# polarization_switch_mid_redo.net
KiCad netlist of a schematic drawn in EAGLE
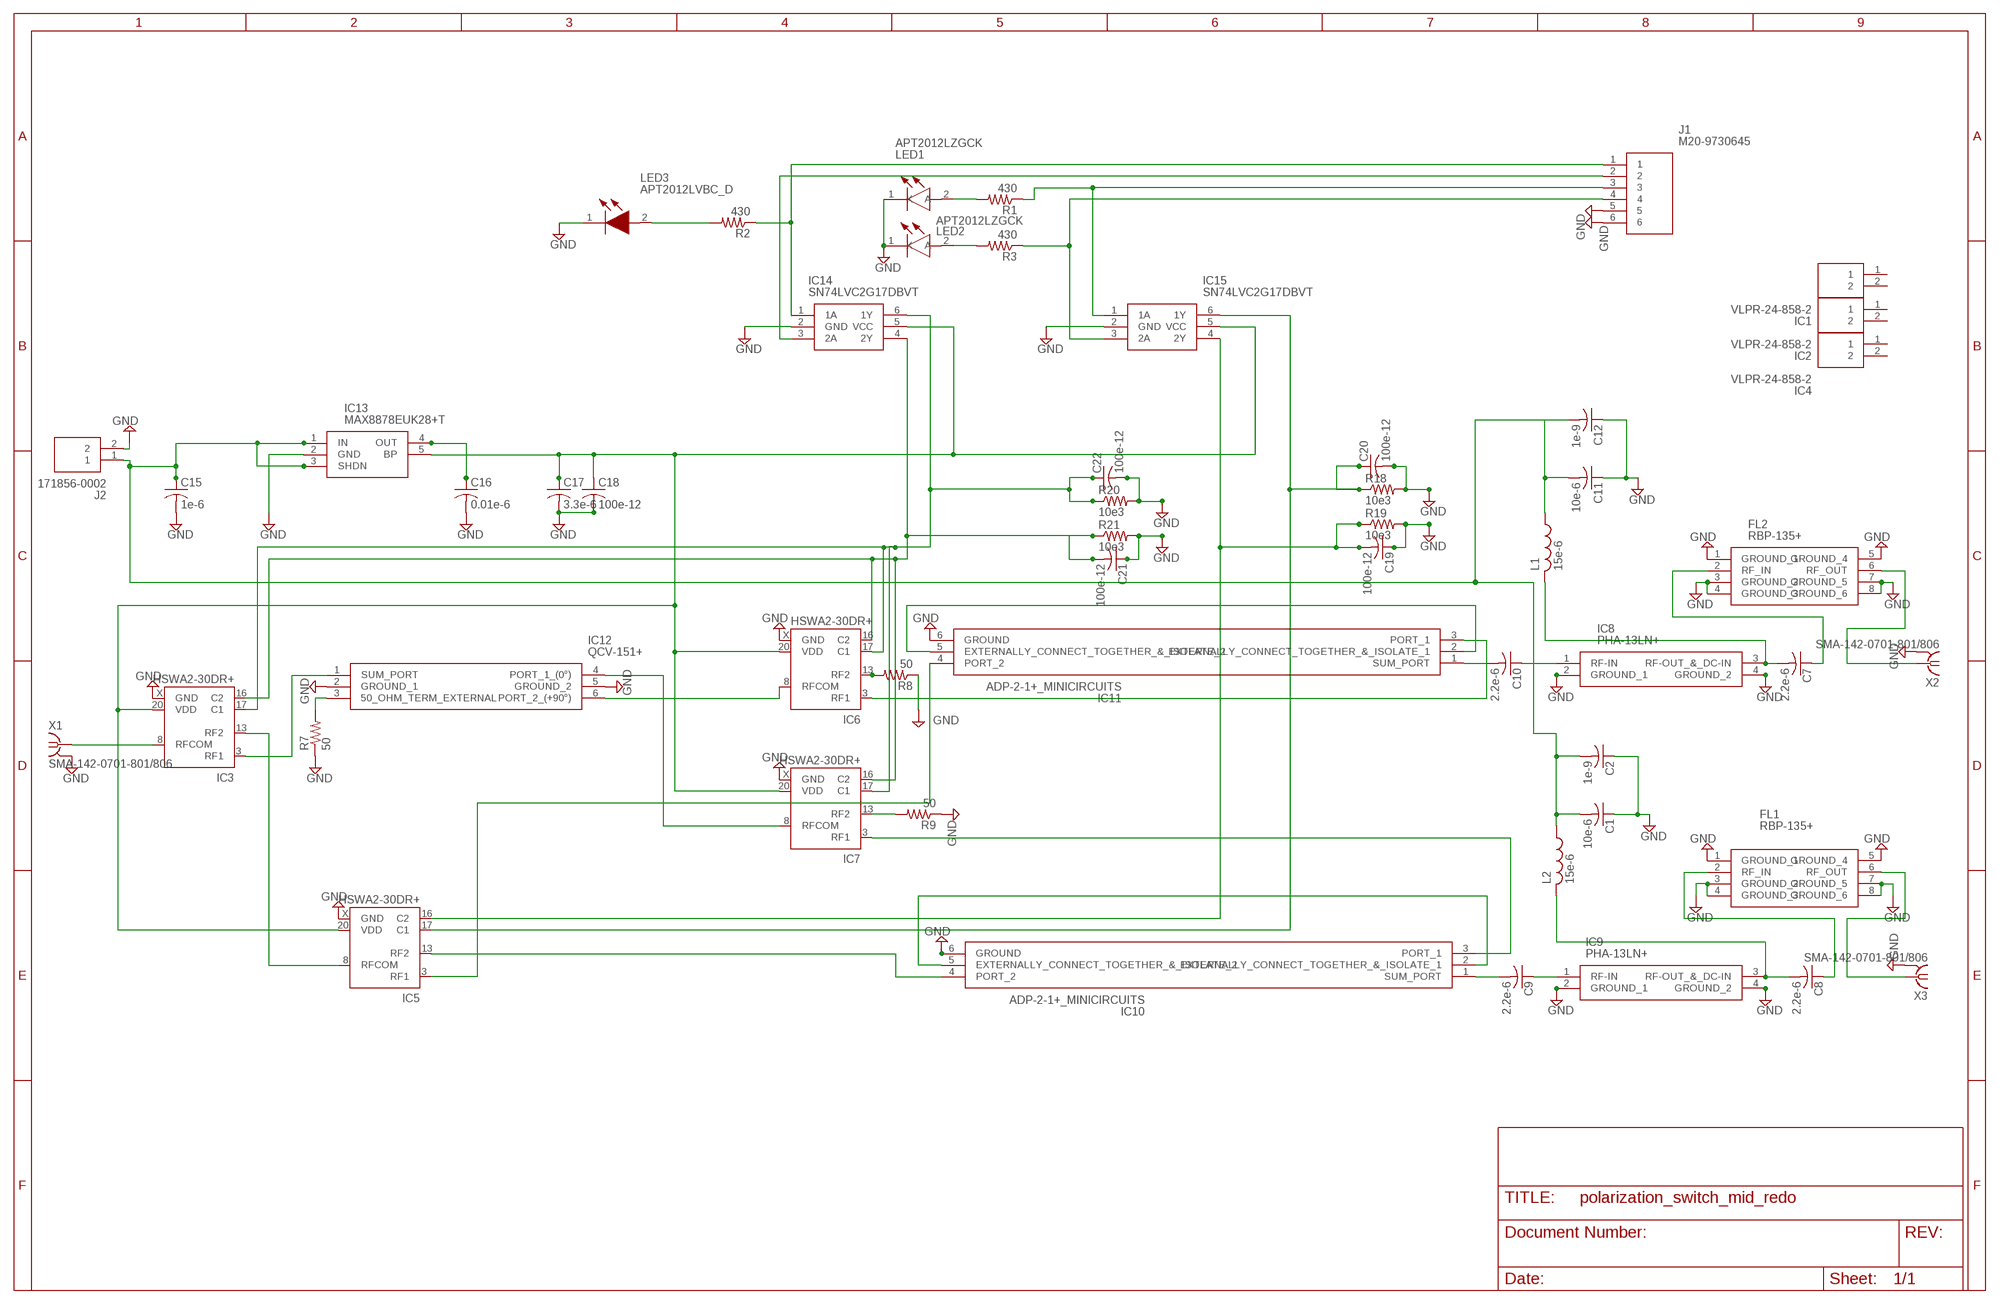
[diagram p0: schematic, sheet 1]

(export (version "E")
  (design (tool "Eeschema 10.0.6"))
  (components
    (comp (ref "C1")
      (value "10e-6")
      (footprint "eagle-import:C0603")
      (libsource (lib "eagle-import") (part "C-USC0603"))
    )
    (comp (ref "C2")
      (value "1e-9")
      (footprint "eagle-import:C0603")
      (libsource (lib "eagle-import") (part "C-USC0603"))
    )
    (comp (ref "C7")
      (value "2.2e-6")
      (footprint "eagle-import:C0603")
      (libsource (lib "eagle-import") (part "C-USC0603"))
    )
    (comp (ref "C8")
      (value "2.2e-6")
      (footprint "eagle-import:C0603")
      (libsource (lib "eagle-import") (part "C-USC0603"))
    )
    (comp (ref "C9")
      (value "2.2e-6")
      (footprint "eagle-import:C0603")
      (libsource (lib "eagle-import") (part "C-USC0603"))
    )
    (comp (ref "C10")
      (value "2.2e-6")
      (footprint "eagle-import:C0603")
      (libsource (lib "eagle-import") (part "C-USC0603"))
    )
    (comp (ref "C11")
      (value "10e-6")
      (footprint "eagle-import:C0603")
      (libsource (lib "eagle-import") (part "C-USC0603"))
    )
    (comp (ref "C12")
      (value "1e-9")
      (footprint "eagle-import:C0603")
      (libsource (lib "eagle-import") (part "C-USC0603"))
    )
    (comp (ref "C15")
      (value "1e-6")
      (footprint "eagle-import:C0603")
      (libsource (lib "eagle-import") (part "C-USC0603"))
    )
    (comp (ref "C16")
      (value "0.01e-6")
      (footprint "eagle-import:C0603")
      (libsource (lib "eagle-import") (part "C-USC0603"))
    )
    (comp (ref "C17")
      (value "3.3e-6")
      (footprint "eagle-import:C0603")
      (libsource (lib "eagle-import") (part "C-USC0603"))
    )
    (comp (ref "C18")
      (value "100e-12")
      (footprint "eagle-import:C0603")
      (libsource (lib "eagle-import") (part "C-USC0603"))
    )
    (comp (ref "C19")
      (value "100e-12")
      (footprint "eagle-import:C0603")
      (libsource (lib "eagle-import") (part "C-USC0603"))
    )
    (comp (ref "C20")
      (value "100e-12")
      (footprint "eagle-import:C0603")
      (libsource (lib "eagle-import") (part "C-USC0603"))
    )
    (comp (ref "C21")
      (value "100e-12")
      (footprint "eagle-import:C0603")
      (libsource (lib "eagle-import") (part "C-USC0603"))
    )
    (comp (ref "C22")
      (value "100e-12")
      (footprint "eagle-import:C0603")
      (libsource (lib "eagle-import") (part "C-USC0603"))
    )
    (comp (ref "FL1")
      (value "RBP-135+")
      (footprint "eagle-import:RBP135")
      (libsource (lib "eagle-import") (part "RBP-135+"))
    )
    (comp (ref "FL2")
      (value "RBP-135+")
      (footprint "eagle-import:RBP135")
      (libsource (lib "eagle-import") (part "RBP-135+"))
    )
    (comp (ref "IC1")
      (value "VLPR-24-858-2")
      (footprint "eagle-import:VLPR248582")
      (fields (field (name "RS_PART_NUMBER") "9063748"))
      (libsource (lib "eagle-import") (part "VLPR-24-858-2"))
    )
    (comp (ref "IC2")
      (value "VLPR-24-858-2")
      (footprint "eagle-import:VLPR248582")
      (fields (field (name "RS_PART_NUMBER") "9063748"))
      (libsource (lib "eagle-import") (part "VLPR-24-858-2"))
    )
    (comp (ref "IC3")
      (value "HSWA2-30DR+")
      (footprint "eagle-import:DG983-1")
      (libsource (lib "eagle-import") (part "HSWA2-30DR+"))
    )
    (comp (ref "IC4")
      (value "VLPR-24-858-2")
      (footprint "eagle-import:VLPR248582")
      (fields (field (name "RS_PART_NUMBER") "9063748"))
      (libsource (lib "eagle-import") (part "VLPR-24-858-2"))
    )
    (comp (ref "IC5")
      (value "HSWA2-30DR+")
      (footprint "eagle-import:DG983-1")
      (libsource (lib "eagle-import") (part "HSWA2-30DR+"))
    )
    (comp (ref "IC6")
      (value "HSWA2-30DR+")
      (footprint "eagle-import:DG983-1")
      (libsource (lib "eagle-import") (part "HSWA2-30DR+"))
    )
    (comp (ref "IC7")
      (value "HSWA2-30DR+")
      (footprint "eagle-import:DG983-1")
      (libsource (lib "eagle-import") (part "HSWA2-30DR+"))
    )
    (comp (ref "IC8")
      (value "PHA-13LN+")
      (footprint "eagle-import:PHA13LN")
      (libsource (lib "eagle-import") (part "PHA-13LN+"))
    )
    (comp (ref "IC9")
      (value "PHA-13LN+")
      (footprint "eagle-import:PHA13LN")
      (libsource (lib "eagle-import") (part "PHA-13LN+"))
    )
    (comp (ref "IC10")
      (value "ADP-2-1+_MINICIRCUITS")
      (footprint "eagle-import:SOTFL254P691X411-6N")
      (fields (field (name "MANUFACTURER_PART_NUMBER") "ADP-2-1+ MINICIRCUITS"))
      (libsource (lib "eagle-import") (part "ADP-2-1+_MINICIRCUITS"))
    )
    (comp (ref "IC11")
      (value "ADP-2-1+_MINICIRCUITS")
      (footprint "eagle-import:SOTFL254P691X411-6N")
      (fields (field (name "MANUFACTURER_PART_NUMBER") "ADP-2-1+ MINICIRCUITS"))
      (libsource (lib "eagle-import") (part "ADP-2-1+_MINICIRCUITS"))
    )
    (comp (ref "IC12")
      (value "QCV-151+")
      (footprint "eagle-import:QCV151")
      (libsource (lib "eagle-import") (part "QCV-151+"))
    )
    (comp (ref "IC13")
      (value "MAX8878EUK28+T")
      (footprint "eagle-import:SOT95P280X145-5N")
      (libsource (lib "eagle-import") (part "MAX8878EUK28+T"))
    )
    (comp (ref "IC14")
      (value "SN74LVC2G17DBVT")
      (footprint "eagle-import:SOT95P280X145-6N")
      (fields
        (field (name "MOUSER_PART_NUMBER") "595-SN74LVC2G17DBVT")
        (field (name "RS_PART_NUMBER") "6628944P")
      )
      (libsource (lib "eagle-import") (part "SN74LVC2G17DBVT"))
    )
    (comp (ref "IC15")
      (value "SN74LVC2G17DBVT")
      (footprint "eagle-import:SOT95P280X145-6N")
      (fields
        (field (name "MOUSER_PART_NUMBER") "595-SN74LVC2G17DBVT")
        (field (name "RS_PART_NUMBER") "6628944P")
      )
      (libsource (lib "eagle-import") (part "SN74LVC2G17DBVT"))
    )
    (comp (ref "J1")
      (value "M20-9730645")
      (footprint "eagle-import:HDRV6W66P0X254_1X6_1524X254X96")
      (fields (field (name "MOUSER_PART_NUMBER") "855-M20-9730645"))
      (libsource (lib "eagle-import") (part "M20-9730645"))
    )
    (comp (ref "J2")
      (value "171856-0002")
      (footprint "eagle-import:SHDR2W90P0X254_1X2_493X635X106")
      (fields
        (field (name "MOUSER_PART_NUMBER") "538-171856-0002")
        (field (name "RS_PART_NUMBER") "7922884P")
      )
      (libsource (lib "eagle-import") (part "171856-0002"))
    )
    (comp (ref "L1")
      (value "15e-6")
      (footprint "eagle-import:L3225M")
      (libsource (lib "eagle-import") (part "L-USL3225M"))
    )
    (comp (ref "L2")
      (value "15e-6")
      (footprint "eagle-import:L3225M")
      (libsource (lib "eagle-import") (part "L-USL3225M"))
    )
    (comp (ref "LED1")
      (value "APT2012LZGCK")
      (footprint "eagle-import:LEDC2012X85N")
      (fields (field (name "MOUSER_PART_NUMBER") "604-APT2012LZGCK"))
      (libsource (lib "eagle-import") (part "APT2012LZGCK"))
    )
    (comp (ref "LED2")
      (value "APT2012LZGCK")
      (footprint "eagle-import:LEDC2012X85N")
      (fields (field (name "MOUSER_PART_NUMBER") "604-APT2012LZGCK"))
      (libsource (lib "eagle-import") (part "APT2012LZGCK"))
    )
    (comp (ref "LED3")
      (value "APT2012LVBC_D")
      (footprint "eagle-import:LEDC2012X85N")
      (fields
        (field (name "ARROW_PART_NUMBER") "APT2012LVBC/D")
        (field (name "MOUSER_PART_NUMBER") "604-APT2012LVBCD")
      )
      (libsource (lib "eagle-import") (part "APT2012LVBC_D"))
    )
    (comp (ref "R1")
      (value "430")
      (footprint "eagle-import:R0603")
      (libsource (lib "eagle-import") (part "R-US_R0603"))
    )
    (comp (ref "R2")
      (value "430")
      (footprint "eagle-import:R0603")
      (libsource (lib "eagle-import") (part "R-US_R0603"))
    )
    (comp (ref "R3")
      (value "430")
      (footprint "eagle-import:R0603")
      (libsource (lib "eagle-import") (part "R-US_R0603"))
    )
    (comp (ref "R7")
      (value "50")
      (footprint "eagle-import:R0603")
      (libsource (lib "eagle-import") (part "R-US_R0603"))
    )
    (comp (ref "R8")
      (value "50")
      (footprint "eagle-import:R0603")
      (libsource (lib "eagle-import") (part "R-US_R0603"))
    )
    (comp (ref "R9")
      (value "50")
      (footprint "eagle-import:R0603")
      (libsource (lib "eagle-import") (part "R-US_R0603"))
    )
    (comp (ref "R18")
      (value "10e3")
      (footprint "eagle-import:R0603")
      (libsource (lib "eagle-import") (part "R-US_R0603"))
    )
    (comp (ref "R19")
      (value "10e3")
      (footprint "eagle-import:R0603")
      (libsource (lib "eagle-import") (part "R-US_R0603"))
    )
    (comp (ref "R20")
      (value "10e3")
      (footprint "eagle-import:R0603")
      (libsource (lib "eagle-import") (part "R-US_R0603"))
    )
    (comp (ref "R21")
      (value "10e3")
      (footprint "eagle-import:R0603")
      (libsource (lib "eagle-import") (part "R-US_R0603"))
    )
    (comp (ref "X1")
      (value "SMA-142-0701-801/806")
      (footprint "eagle-import:J502-ND-142-0701-801_806")
      (fields (field (name "MF") "JOHNSON COMPONENTS") (field (name "MPN") "142-0701-801"))
      (libsource (lib "eagle-import") (part "SMA-142-0701-801/806"))
    )
    (comp (ref "X2")
      (value "SMA-142-0701-801/806")
      (footprint "eagle-import:J502-ND-142-0701-801_806")
      (fields (field (name "MF") "JOHNSON COMPONENTS") (field (name "MPN") "142-0701-801"))
      (libsource (lib "eagle-import") (part "SMA-142-0701-801/806"))
    )
    (comp (ref "X3")
      (value "SMA-142-0701-801/806")
      (footprint "eagle-import:J502-ND-142-0701-801_806")
      (fields (field (name "MF") "JOHNSON COMPONENTS") (field (name "MPN") "142-0701-801"))
      (libsource (lib "eagle-import") (part "SMA-142-0701-801/806"))
    )
  )
  (nets
    (net (code "1") (name "GND") (class "Default")
      (node (ref "C1") (pin "1") (pinfunction "1_1") (pintype "passive"))
      (node (ref "C11") (pin "1") (pinfunction "1_1") (pintype "passive"))
      (node (ref "C12") (pin "1") (pinfunction "1_1") (pintype "passive"))
      (node (ref "C15") (pin "2") (pinfunction "2_2") (pintype "passive"))
      (node (ref "C16") (pin "2") (pinfunction "2_2") (pintype "passive"))
      (node (ref "C17") (pin "2") (pinfunction "2_2") (pintype "passive"))
      (node (ref "C18") (pin "2") (pinfunction "2_2") (pintype "passive"))
      (node (ref "C19") (pin "1") (pinfunction "1_1") (pintype "passive"))
      (node (ref "C2") (pin "1") (pinfunction "1_1") (pintype "passive"))
      (node (ref "C20") (pin "2") (pinfunction "2_2") (pintype "passive"))
      (node (ref "C21") (pin "1") (pinfunction "1_1") (pintype "passive"))
      (node (ref "C22") (pin "2") (pinfunction "2_2") (pintype "passive"))
      (node (ref "FL1") (pin "1") (pinfunction "GROUND_1_1") (pintype "bidirectional"))
      (node (ref "FL1") (pin "3") (pinfunction "GROUND_2_3") (pintype "bidirectional"))
      (node (ref "FL1") (pin "4") (pinfunction "GROUND_3_4") (pintype "bidirectional"))
      (node (ref "FL1") (pin "5") (pinfunction "GROUND_4_5") (pintype "bidirectional"))
      (node (ref "FL1") (pin "7") (pinfunction "GROUND_5_7") (pintype "bidirectional"))
      (node (ref "FL1") (pin "8") (pinfunction "GROUND_6_8") (pintype "bidirectional"))
      (node (ref "FL2") (pin "1") (pinfunction "GROUND_1_1") (pintype "bidirectional"))
      (node (ref "FL2") (pin "3") (pinfunction "GROUND_2_3") (pintype "bidirectional"))
      (node (ref "FL2") (pin "4") (pinfunction "GROUND_3_4") (pintype "bidirectional"))
      (node (ref "FL2") (pin "5") (pinfunction "GROUND_4_5") (pintype "bidirectional"))
      (node (ref "FL2") (pin "7") (pinfunction "GROUND_5_7") (pintype "bidirectional"))
      (node (ref "FL2") (pin "8") (pinfunction "GROUND_6_8") (pintype "bidirectional"))
      (node (ref "IC10") (pin "6") (pinfunction "GROUND_6") (pintype "bidirectional"))
      (node (ref "IC11") (pin "6") (pinfunction "GROUND_6") (pintype "bidirectional"))
      (node (ref "IC12") (pin "2") (pinfunction "GROUND_1_2") (pintype "bidirectional"))
      (node (ref "IC12") (pin "5") (pinfunction "GROUND_2_5") (pintype "bidirectional"))
      (node (ref "IC13") (pin "2") (pinfunction "GND_2") (pintype "power_in"))
      (node (ref "IC14") (pin "2") (pinfunction "GND_2") (pintype "bidirectional"))
      (node (ref "IC15") (pin "2") (pinfunction "GND_2") (pintype "bidirectional"))
      (node (ref "IC3") (pin "X") (pinfunction "GND_X") (pintype "power_in"))
      (node (ref "IC5") (pin "X") (pinfunction "GND_X") (pintype "power_in"))
      (node (ref "IC6") (pin "X") (pinfunction "GND_X") (pintype "power_in"))
      (node (ref "IC7") (pin "X") (pinfunction "GND_X") (pintype "power_in"))
      (node (ref "IC8") (pin "2") (pinfunction "GROUND_1_2") (pintype "bidirectional"))
      (node (ref "IC8") (pin "4") (pinfunction "GROUND_2_4") (pintype "bidirectional"))
      (node (ref "IC9") (pin "2") (pinfunction "GROUND_1_2") (pintype "bidirectional"))
      (node (ref "IC9") (pin "4") (pinfunction "GROUND_2_4") (pintype "bidirectional"))
      (node (ref "J1") (pin "5") (pinfunction "5_5") (pintype "bidirectional"))
      (node (ref "J1") (pin "6") (pinfunction "6_6") (pintype "bidirectional"))
      (node (ref "J2") (pin "2") (pinfunction "2_2") (pintype "bidirectional"))
      (node (ref "LED1") (pin "1") (pinfunction "K_1") (pintype "bidirectional"))
      (node (ref "LED2") (pin "1") (pinfunction "K_1") (pintype "bidirectional"))
      (node (ref "LED3") (pin "1") (pinfunction "K_1") (pintype "bidirectional"))
      (node (ref "R18") (pin "2") (pinfunction "2_2") (pintype "passive"))
      (node (ref "R19") (pin "2") (pinfunction "2_2") (pintype "passive"))
      (node (ref "R20") (pin "2") (pinfunction "2_2") (pintype "passive"))
      (node (ref "R21") (pin "2") (pinfunction "2_2") (pintype "passive"))
      (node (ref "R7") (pin "1") (pinfunction "1_1") (pintype "passive"))
      (node (ref "R8") (pin "1") (pinfunction "1_1") (pintype "passive"))
      (node (ref "R9") (pin "1") (pinfunction "1_1") (pintype "passive"))
      (node (ref "X1") (pin "G@1") (pinfunction "2_G@1") (pintype "passive"))
      (node (ref "X1") (pin "G@2") (pinfunction "2_G@2") (pintype "passive"))
      (node (ref "X1") (pin "G@3") (pinfunction "2_G@3") (pintype "passive"))
      (node (ref "X1") (pin "G@4") (pinfunction "2_G@4") (pintype "passive"))
      (node (ref "X2") (pin "G@1") (pinfunction "2_G@1") (pintype "passive"))
      (node (ref "X2") (pin "G@2") (pinfunction "2_G@2") (pintype "passive"))
      (node (ref "X2") (pin "G@3") (pinfunction "2_G@3") (pintype "passive"))
      (node (ref "X2") (pin "G@4") (pinfunction "2_G@4") (pintype "passive"))
      (node (ref "X3") (pin "G@1") (pinfunction "2_G@1") (pintype "passive"))
      (node (ref "X3") (pin "G@2") (pinfunction "2_G@2") (pintype "passive"))
      (node (ref "X3") (pin "G@3") (pinfunction "2_G@3") (pintype "passive"))
      (node (ref "X3") (pin "G@4") (pinfunction "2_G@4") (pintype "passive"))
    )
    (net (code "2") (name "Net-(FL1-RF_IN)") (class "Default")
      (node (ref "C8") (pin "1") (pinfunction "1_1") (pintype "passive"))
      (node (ref "FL1") (pin "2") (pinfunction "RF_IN_2") (pintype "bidirectional"))
    )
    (net (code "3") (name "Net-(FL1-RF_OUT)") (class "Default")
      (node (ref "FL1") (pin "6") (pinfunction "RF_OUT_6") (pintype "bidirectional"))
      (node (ref "X3") (pin "1") (pinfunction "1_1") (pintype "passive"))
    )
    (net (code "4") (name "Net-(FL2-RF_IN)") (class "Default")
      (node (ref "C7") (pin "1") (pinfunction "1_1") (pintype "passive"))
      (node (ref "FL2") (pin "2") (pinfunction "RF_IN_2") (pintype "bidirectional"))
    )
    (net (code "5") (name "Net-(FL2-RF_OUT)") (class "Default")
      (node (ref "FL2") (pin "6") (pinfunction "RF_OUT_6") (pintype "bidirectional"))
      (node (ref "X2") (pin "1") (pinfunction "1_1") (pintype "passive"))
    )
    (net (code "6") (name "Net-(IC3A-RF2)") (class "Default")
      (node (ref "IC3") (pin "13") (pinfunction "RF2_13") (pintype "passive"))
      (node (ref "IC5") (pin "8") (pinfunction "RFCOM_8") (pintype "passive"))
    )
    (net (code "7") (name "Net-(IC3A-RFCOM)") (class "Default")
      (node (ref "IC3") (pin "8") (pinfunction "RFCOM_8") (pintype "passive"))
      (node (ref "X1") (pin "1") (pinfunction "1_1") (pintype "passive"))
    )
    (net (code "8") (name "Net-(IC6A-RF2)") (class "Default")
      (node (ref "IC6") (pin "13") (pinfunction "RF2_13") (pintype "passive"))
      (node (ref "R8") (pin "2") (pinfunction "2_2") (pintype "passive"))
    )
    (net (code "9") (name "Net-(IC7A-RF2)") (class "Default")
      (node (ref "IC7") (pin "13") (pinfunction "RF2_13") (pintype "passive"))
      (node (ref "R9") (pin "2") (pinfunction "2_2") (pintype "passive"))
    )
    (net (code "10") (name "Net-(IC8-RF-IN)") (class "Default")
      (node (ref "C10") (pin "1") (pinfunction "1_1") (pintype "passive"))
      (node (ref "IC8") (pin "1") (pinfunction "RF-IN_1") (pintype "bidirectional"))
    )
    (net (code "11") (name "Net-(IC8-RF-OUT_&_DC-IN)") (class "Default")
      (node (ref "C7") (pin "2") (pinfunction "2_2") (pintype "passive"))
      (node (ref "IC8") (pin "3") (pinfunction "RF-OUT_&_DC-IN_3") (pintype "bidirectional"))
      (node (ref "L1") (pin "2") (pinfunction "2_2") (pintype "passive"))
    )
    (net (code "12") (name "Net-(IC9-RF-IN)") (class "Default")
      (node (ref "C9") (pin "1") (pinfunction "1_1") (pintype "passive"))
      (node (ref "IC9") (pin "1") (pinfunction "RF-IN_1") (pintype "bidirectional"))
    )
    (net (code "13") (name "Net-(IC9-RF-OUT_&_DC-IN)") (class "Default")
      (node (ref "C8") (pin "2") (pinfunction "2_2") (pintype "passive"))
      (node (ref "IC9") (pin "3") (pinfunction "RF-OUT_&_DC-IN_3") (pintype "bidirectional"))
      (node (ref "L2") (pin "2") (pinfunction "2_2") (pintype "passive"))
    )
    (net (code "14") (name "Net-(IC10-EXTERNALLY_CONNECT_TOGETHER_&_ISOLATE_1)") (class "Default")
      (node (ref "IC10") (pin "2") (pinfunction "EXTERNALLY_CONNECT_TOGETHER_&_ISOLATE_1_2") (pintype "bidirectional"))
      (node (ref "IC10") (pin "5") (pinfunction "EXTERNALLY_CONNECT_TOGETHER_&_ISOLATE_2_5") (pintype "bidirectional"))
    )
    (net (code "15") (name "Net-(IC10-PORT_1)") (class "Default")
      (node (ref "IC10") (pin "3") (pinfunction "PORT_1_3") (pintype "bidirectional"))
      (node (ref "IC7") (pin "3") (pinfunction "RF1_3") (pintype "passive"))
    )
    (net (code "16") (name "Net-(IC10-PORT_2)") (class "Default")
      (node (ref "IC10") (pin "4") (pinfunction "PORT_2_4") (pintype "bidirectional"))
      (node (ref "IC5") (pin "13") (pinfunction "RF2_13") (pintype "passive"))
    )
    (net (code "17") (name "Net-(IC10-SUM_PORT)") (class "Default")
      (node (ref "C9") (pin "2") (pinfunction "2_2") (pintype "passive"))
      (node (ref "IC10") (pin "1") (pinfunction "SUM_PORT_1") (pintype "bidirectional"))
    )
    (net (code "18") (name "Net-(IC11-EXTERNALLY_CONNECT_TOGETHER_&_ISOLATE_1)") (class "Default")
      (node (ref "IC11") (pin "2") (pinfunction "EXTERNALLY_CONNECT_TOGETHER_&_ISOLATE_1_2") (pintype "bidirectional"))
      (node (ref "IC11") (pin "5") (pinfunction "EXTERNALLY_CONNECT_TOGETHER_&_ISOLATE_2_5") (pintype "bidirectional"))
    )
    (net (code "19") (name "Net-(IC11-PORT_1)") (class "Default")
      (node (ref "IC11") (pin "3") (pinfunction "PORT_1_3") (pintype "bidirectional"))
      (node (ref "IC6") (pin "3") (pinfunction "RF1_3") (pintype "passive"))
    )
    (net (code "20") (name "Net-(IC11-PORT_2)") (class "Default")
      (node (ref "IC11") (pin "4") (pinfunction "PORT_2_4") (pintype "bidirectional"))
      (node (ref "IC5") (pin "3") (pinfunction "RF1_3") (pintype "passive"))
    )
    (net (code "21") (name "Net-(IC11-SUM_PORT)") (class "Default")
      (node (ref "C10") (pin "2") (pinfunction "2_2") (pintype "passive"))
      (node (ref "IC11") (pin "1") (pinfunction "SUM_PORT_1") (pintype "bidirectional"))
    )
    (net (code "22") (name "Net-(IC12-50_OHM_TERM_EXTERNAL)") (class "Default")
      (node (ref "IC12") (pin "3") (pinfunction "50_OHM_TERM_EXTERNAL_3") (pintype "bidirectional"))
      (node (ref "R7") (pin "2") (pinfunction "2_2") (pintype "passive"))
    )
    (net (code "23") (name "Net-(IC12-PORT_1_(0°))") (class "Default")
      (node (ref "IC12") (pin "4") (pinfunction "PORT_1_(0°)_4") (pintype "bidirectional"))
      (node (ref "IC7") (pin "8") (pinfunction "RFCOM_8") (pintype "passive"))
    )
    (net (code "24") (name "Net-(IC12-PORT_2_(+90°))") (class "Default")
      (node (ref "IC12") (pin "6") (pinfunction "PORT_2_(+90°)_6") (pintype "bidirectional"))
      (node (ref "IC6") (pin "8") (pinfunction "RFCOM_8") (pintype "passive"))
    )
    (net (code "25") (name "Net-(IC12-SUM_PORT)") (class "Default")
      (node (ref "IC12") (pin "1") (pinfunction "SUM_PORT_1") (pintype "bidirectional"))
      (node (ref "IC3") (pin "3") (pinfunction "RF1_3") (pintype "passive"))
    )
    (net (code "26") (name "Net-(IC13-BP)") (class "Default")
      (node (ref "C17") (pin "1") (pinfunction "1_1") (pintype "passive"))
      (node (ref "C18") (pin "1") (pinfunction "1_1") (pintype "passive"))
      (node (ref "IC13") (pin "5") (pinfunction "BP_5") (pintype "bidirectional"))
      (node (ref "IC14") (pin "5") (pinfunction "VCC_5") (pintype "bidirectional"))
      (node (ref "IC15") (pin "5") (pinfunction "VCC_5") (pintype "bidirectional"))
      (node (ref "IC3") (pin "20") (pinfunction "VDD_20") (pintype "input"))
      (node (ref "IC5") (pin "20") (pinfunction "VDD_20") (pintype "input"))
      (node (ref "IC6") (pin "20") (pinfunction "VDD_20") (pintype "input"))
      (node (ref "IC7") (pin "20") (pinfunction "VDD_20") (pintype "input"))
    )
    (net (code "27") (name "Net-(IC13-IN)") (class "Default")
      (node (ref "C1") (pin "2") (pinfunction "2_2") (pintype "passive"))
      (node (ref "C11") (pin "2") (pinfunction "2_2") (pintype "passive"))
      (node (ref "C12") (pin "2") (pinfunction "2_2") (pintype "passive"))
      (node (ref "C15") (pin "1") (pinfunction "1_1") (pintype "passive"))
      (node (ref "C2") (pin "2") (pinfunction "2_2") (pintype "passive"))
      (node (ref "IC13") (pin "1") (pinfunction "IN_1") (pintype "input"))
      (node (ref "IC13") (pin "3") (pinfunction "SHDN_3") (pintype "bidirectional"))
      (node (ref "J2") (pin "1") (pinfunction "1_1") (pintype "bidirectional"))
      (node (ref "L1") (pin "1") (pinfunction "1_1") (pintype "passive"))
      (node (ref "L2") (pin "1") (pinfunction "1_1") (pintype "passive"))
    )
    (net (code "28") (name "Net-(IC13-OUT)") (class "Default")
      (node (ref "C16") (pin "1") (pinfunction "1_1") (pintype "passive"))
      (node (ref "IC13") (pin "4") (pinfunction "OUT_4") (pintype "output"))
    )
    (net (code "29") (name "Net-(IC14-1A)") (class "Default")
      (node (ref "IC14") (pin "1") (pinfunction "1A_1") (pintype "bidirectional"))
      (node (ref "J1") (pin "1") (pinfunction "1_1") (pintype "bidirectional"))
      (node (ref "R2") (pin "1") (pinfunction "1_1") (pintype "passive"))
    )
    (net (code "30") (name "Net-(IC14-1Y)") (class "Default")
      (node (ref "C22") (pin "1") (pinfunction "1_1") (pintype "passive"))
      (node (ref "IC14") (pin "6") (pinfunction "1Y_6") (pintype "bidirectional"))
      (node (ref "IC3") (pin "17") (pinfunction "C1_17") (pintype "passive"))
      (node (ref "IC6") (pin "17") (pinfunction "C1_17") (pintype "passive"))
      (node (ref "IC7") (pin "17") (pinfunction "C1_17") (pintype "passive"))
      (node (ref "R20") (pin "1") (pinfunction "1_1") (pintype "passive"))
    )
    (net (code "31") (name "Net-(IC14-2A)") (class "Default")
      (node (ref "IC14") (pin "3") (pinfunction "2A_3") (pintype "bidirectional"))
      (node (ref "J1") (pin "2") (pinfunction "2_2") (pintype "bidirectional"))
    )
    (net (code "32") (name "Net-(IC14-2Y)") (class "Default")
      (node (ref "C21") (pin "2") (pinfunction "2_2") (pintype "passive"))
      (node (ref "IC14") (pin "4") (pinfunction "2Y_4") (pintype "bidirectional"))
      (node (ref "IC3") (pin "16") (pinfunction "C2_16") (pintype "passive"))
      (node (ref "IC6") (pin "16") (pinfunction "C2_16") (pintype "passive"))
      (node (ref "IC7") (pin "16") (pinfunction "C2_16") (pintype "passive"))
      (node (ref "R21") (pin "1") (pinfunction "1_1") (pintype "passive"))
    )
    (net (code "33") (name "Net-(IC15-1A)") (class "Default")
      (node (ref "IC15") (pin "1") (pinfunction "1A_1") (pintype "bidirectional"))
      (node (ref "J1") (pin "3") (pinfunction "3_3") (pintype "bidirectional"))
      (node (ref "R1") (pin "1") (pinfunction "1_1") (pintype "passive"))
    )
    (net (code "34") (name "Net-(IC15-1Y)") (class "Default")
      (node (ref "C20") (pin "1") (pinfunction "1_1") (pintype "passive"))
      (node (ref "IC15") (pin "6") (pinfunction "1Y_6") (pintype "bidirectional"))
      (node (ref "IC5") (pin "17") (pinfunction "C1_17") (pintype "passive"))
      (node (ref "R18") (pin "1") (pinfunction "1_1") (pintype "passive"))
    )
    (net (code "35") (name "Net-(IC15-2A)") (class "Default")
      (node (ref "IC15") (pin "3") (pinfunction "2A_3") (pintype "bidirectional"))
      (node (ref "J1") (pin "4") (pinfunction "4_4") (pintype "bidirectional"))
      (node (ref "R3") (pin "1") (pinfunction "1_1") (pintype "passive"))
    )
    (net (code "36") (name "Net-(IC15-2Y)") (class "Default")
      (node (ref "C19") (pin "2") (pinfunction "2_2") (pintype "passive"))
      (node (ref "IC15") (pin "4") (pinfunction "2Y_4") (pintype "bidirectional"))
      (node (ref "IC5") (pin "16") (pinfunction "C2_16") (pintype "passive"))
      (node (ref "R19") (pin "1") (pinfunction "1_1") (pintype "passive"))
    )
    (net (code "37") (name "Net-(LED1-A)") (class "Default")
      (node (ref "LED1") (pin "2") (pinfunction "A_2") (pintype "bidirectional"))
      (node (ref "R1") (pin "2") (pinfunction "2_2") (pintype "passive"))
    )
    (net (code "38") (name "Net-(LED2-A)") (class "Default")
      (node (ref "LED2") (pin "2") (pinfunction "A_2") (pintype "bidirectional"))
      (node (ref "R3") (pin "2") (pinfunction "2_2") (pintype "passive"))
    )
    (net (code "39") (name "Net-(LED3-A)") (class "Default")
      (node (ref "LED3") (pin "2") (pinfunction "A_2") (pintype "bidirectional"))
      (node (ref "R2") (pin "2") (pinfunction "2_2") (pintype "passive"))
    )
    (net (code "40") (name "unconnected-(IC1-Pad1)") (class "Default")
      (node (ref "IC1") (pin "1") (pinfunction "1_1") (pintype "bidirectional"))
    )
    (net (code "41") (name "unconnected-(IC1-Pad2)") (class "Default")
      (node (ref "IC1") (pin "2") (pinfunction "2_2") (pintype "bidirectional"))
    )
    (net (code "42") (name "unconnected-(IC2-Pad1)") (class "Default")
      (node (ref "IC2") (pin "1") (pinfunction "1_1") (pintype "bidirectional"))
    )
    (net (code "43") (name "unconnected-(IC2-Pad2)") (class "Default")
      (node (ref "IC2") (pin "2") (pinfunction "2_2") (pintype "bidirectional"))
    )
    (net (code "44") (name "unconnected-(IC4-Pad1)") (class "Default")
      (node (ref "IC4") (pin "1") (pinfunction "1_1") (pintype "bidirectional"))
    )
    (net (code "45") (name "unconnected-(IC4-Pad2)") (class "Default")
      (node (ref "IC4") (pin "2") (pinfunction "2_2") (pintype "bidirectional"))
    )
  )
)
